# 12_IR.net
KiCad netlist of a schematic drawn in Altium Designer
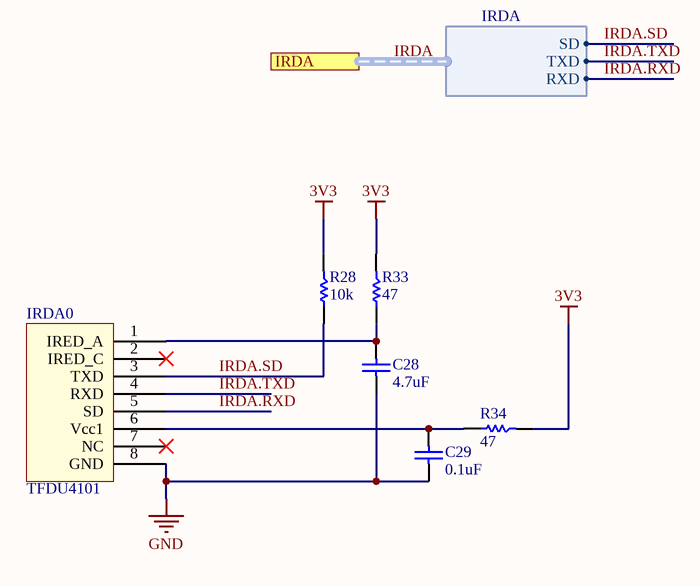
[diagram p0: 12_IR.SchDoc]

(export (version "E")
  (design (tool "Eeschema 10.0.6"))
  (components
    (comp (ref "C28")
      (value "4.7uF")
      (footprint "CAP0805R")
      (description "Capacitor")
      (libsource (lib "Quatro_SchLib") (part "C"))
    )
    (comp (ref "C29")
      (value "0.1uF")
      (footprint "CAP0603R")
      (description "Capacitor")
      (libsource (lib "Quatro_SchLib") (part "C"))
    )
    (comp (ref "IRDA0")
      (value "TFDU4101")
      (footprint "TFDU4101")
      (libsource (lib "Quatro_SchLib") (part "TFDU4101"))
    )
    (comp (ref "R28")
      (value "10k")
      (footprint "RES0603R")
      (description "Resistor")
      (libsource (lib "Quatro_SchLib") (part "R"))
    )
    (comp (ref "R33")
      (value "47")
      (footprint "RES0603R")
      (description "Resistor")
      (libsource (lib "Quatro_SchLib") (part "R"))
    )
    (comp (ref "R34")
      (value "47")
      (footprint "RES0603R")
      (description "Resistor")
      (libsource (lib "Quatro_SchLib") (part "R"))
    )
  )
  (nets
    (net (code "2") (name "/IRDA.RXD") (class "Default")
      (node (ref "IRDA0") (pin "5") (pinfunction "SD_5") (pintype "passive"))
    )
    (net (code "3") (name "/IRDA.SD") (class "Default")
      (node (ref "IRDA0") (pin "3") (pinfunction "TXD_3") (pintype "passive"))
      (node (ref "R28") (pin "2") (pintype "passive"))
    )
    (net (code "4") (name "/IRDA.TXD") (class "Default")
      (node (ref "IRDA0") (pin "4") (pinfunction "RXD_4") (pintype "passive"))
    )
    (net (code "6") (name "3V3") (class "Default")
      (node (ref "R28") (pin "1") (pintype "passive"))
      (node (ref "R33") (pin "1") (pintype "passive"))
      (node (ref "R34") (pin "1") (pintype "passive"))
    )
    (net (code "7") (name "GND") (class "Default")
      (node (ref "C28") (pin "1") (pinfunction "1_1") (pintype "passive"))
      (node (ref "C29") (pin "2") (pinfunction "2_2") (pintype "passive"))
      (node (ref "IRDA0") (pin "8") (pinfunction "GND_8") (pintype "passive"))
    )
    (net (code "8") (name "Net-(IRDA0-IRED_A)") (class "Default")
      (node (ref "C28") (pin "2") (pinfunction "2_2") (pintype "passive"))
      (node (ref "IRDA0") (pin "1") (pinfunction "IRED_A_1") (pintype "passive"))
      (node (ref "R33") (pin "2") (pintype "passive"))
    )
    (net (code "9") (name "Net-(IRDA0-Vcc1)") (class "Default")
      (node (ref "C29") (pin "1") (pinfunction "1_1") (pintype "passive"))
      (node (ref "IRDA0") (pin "6") (pinfunction "Vcc1_6") (pintype "passive"))
      (node (ref "R34") (pin "2") (pintype "passive"))
    )
    (net (code "10") (name "unconnected-(IRDA0-IRED_C-Pad2)") (class "Default")
      (node (ref "IRDA0") (pin "2") (pinfunction "IRED_C_2") (pintype "passive+no_connect"))
    )
    (net (code "11") (name "unconnected-(IRDA0-NC-Pad7)") (class "Default")
      (node (ref "IRDA0") (pin "7") (pinfunction "NC_7") (pintype "passive+no_connect"))
    )
  )
)
